# Supplemental_Power_Switch_System.net
KiCad netlist of a schematic drawn in EAGLE
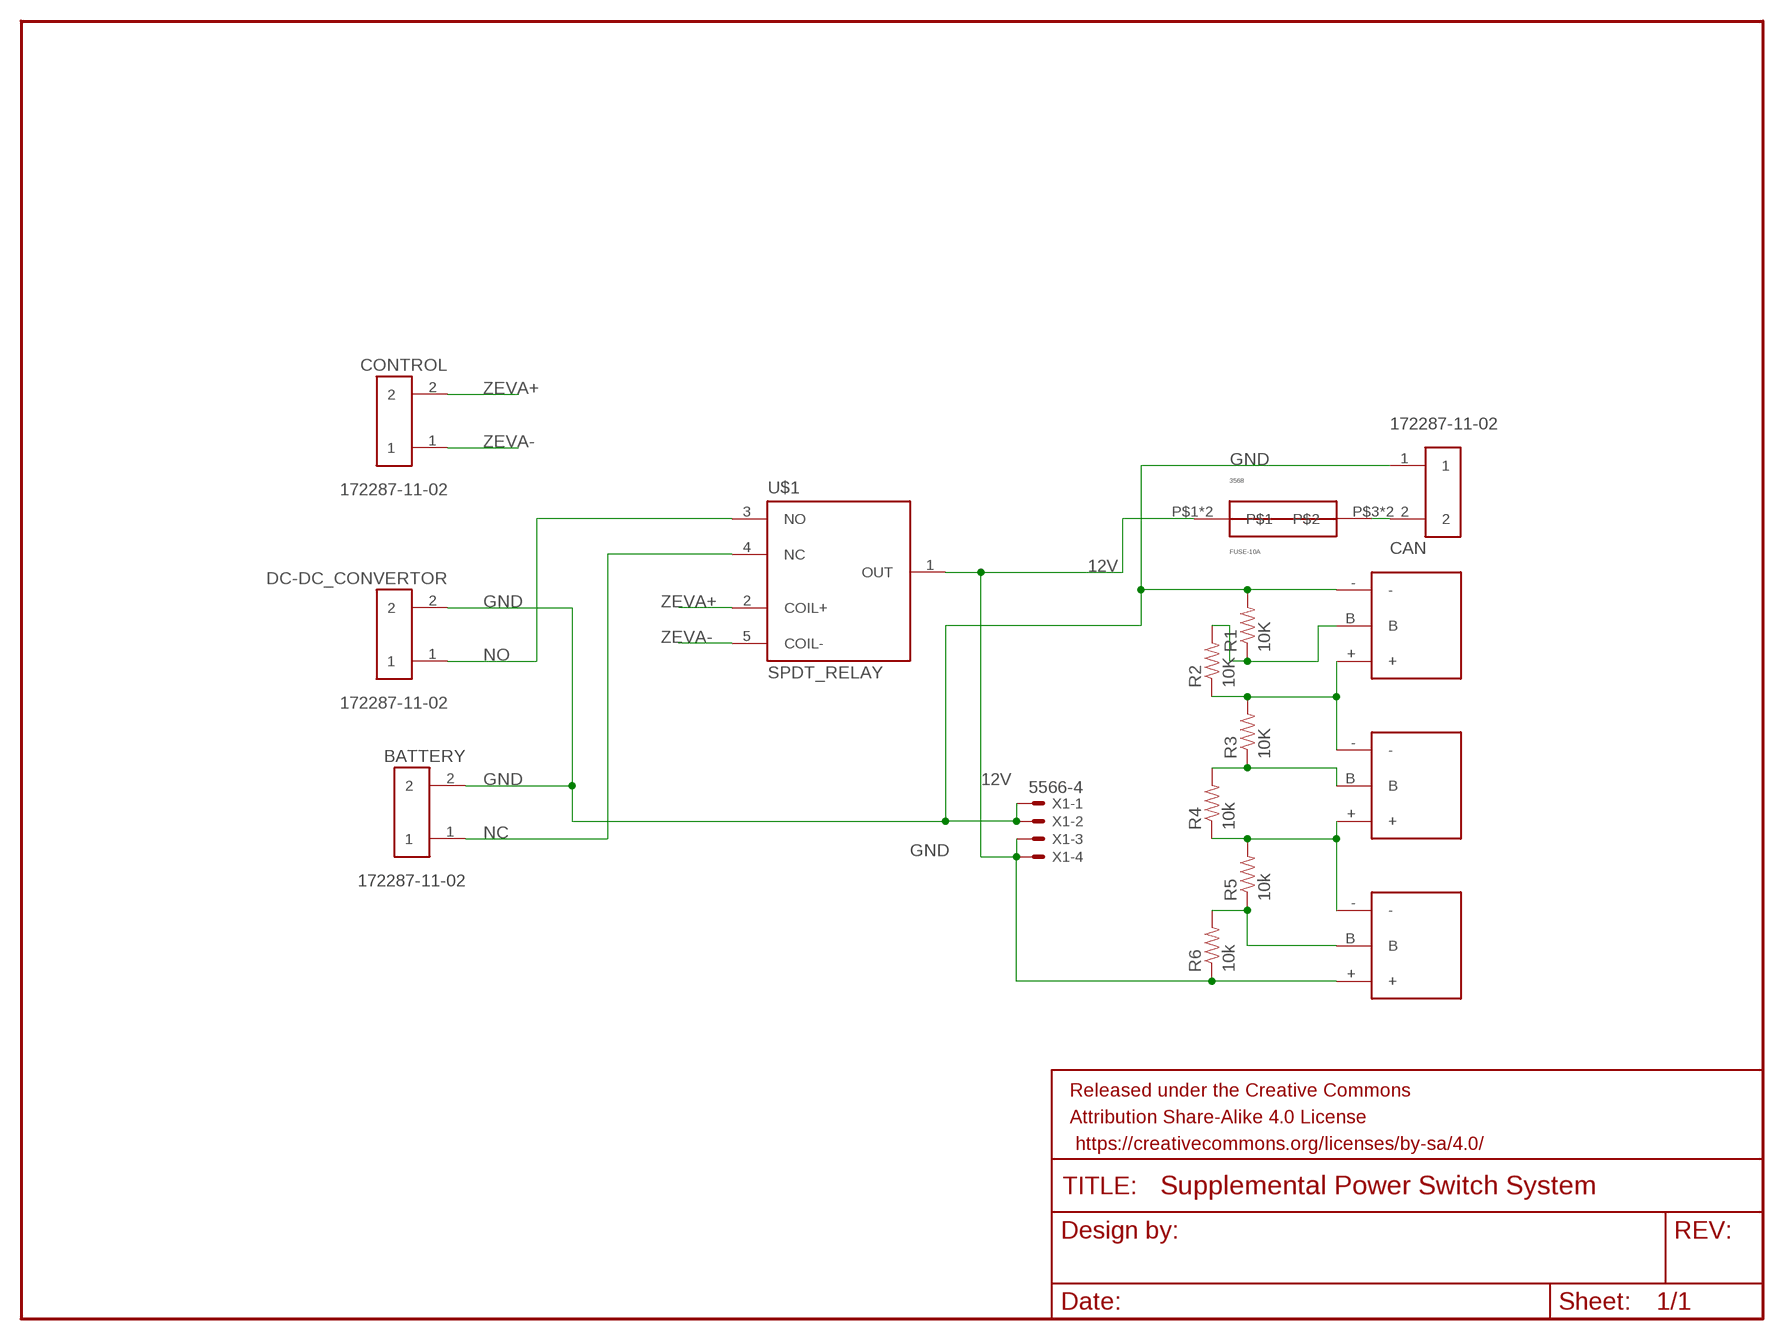
[diagram p0: schematic, sheet 1]

(export (version "E")
  (design (tool "Eeschema 10.0.6"))
  (components
    (comp (ref "BATTERY")
      (value "172287-11-02")
      (footprint "eagle-import:172287-ULTRA-FIT")
      (libsource (lib "eagle-import") (part "172287-11-02"))
    )
    (comp (ref "C1")
      (value "SUPER-CAPACITOR")
      (footprint "eagle-import:DMF")
      (libsource (lib "eagle-import") (part "SUPER-CAPACITOR"))
    )
    (comp (ref "C2")
      (value "SUPER-CAPACITOR")
      (footprint "eagle-import:DMF")
      (libsource (lib "eagle-import") (part "SUPER-CAPACITOR"))
    )
    (comp (ref "C3")
      (value "SUPER-CAPACITOR")
      (footprint "eagle-import:DMF")
      (libsource (lib "eagle-import") (part "SUPER-CAPACITOR"))
    )
    (comp (ref "CAN")
      (value "172287-11-02")
      (footprint "eagle-import:172287-ULTRA-FIT")
      (libsource (lib "eagle-import") (part "172287-11-02"))
    )
    (comp (ref "CONTROL")
      (value "172287-11-02")
      (footprint "eagle-import:172287-ULTRA-FIT")
      (libsource (lib "eagle-import") (part "172287-11-02"))
    )
    (comp (ref "DC-DC_CONVERTOR")
      (value "172287-11-02")
      (footprint "eagle-import:172287-ULTRA-FIT")
      (libsource (lib "eagle-import") (part "172287-11-02"))
    )
    (comp (ref "FRAME1")
      (value "FRAME-LETTERNO_PACKAGE")
      (footprint "eagle-import:DUMMY")
      (fields (field (name "DESIGNER") "Nobody"))
      (libsource (lib "eagle-import") (part "FRAME-LETTERNO_PACKAGE"))
    )
    (comp (ref "FUSE-10A")
      (value "3568")
      (footprint "eagle-import:3568-MINI-297")
      (libsource (lib "eagle-import") (part "3568"))
    )
    (comp (ref "R1")
      (value "10K")
      (footprint "eagle-import:1206")
      (libsource (lib "eagle-import") (part "RESISTOR1206"))
    )
    (comp (ref "R2")
      (value "10K")
      (footprint "eagle-import:1206")
      (libsource (lib "eagle-import") (part "RESISTOR1206"))
    )
    (comp (ref "R3")
      (value "10K")
      (footprint "eagle-import:1206")
      (libsource (lib "eagle-import") (part "RESISTOR1206"))
    )
    (comp (ref "R4")
      (value "10k")
      (footprint "eagle-import:1206")
      (libsource (lib "eagle-import") (part "RESISTOR1206"))
    )
    (comp (ref "R5")
      (value "10k")
      (footprint "eagle-import:1206")
      (libsource (lib "eagle-import") (part "RESISTOR1206"))
    )
    (comp (ref "R6")
      (value "10k")
      (footprint "eagle-import:1206")
      (libsource (lib "eagle-import") (part "RESISTOR1206"))
    )
    (comp (ref "U$1")
      (value "SPDT_RELAY")
      (footprint "eagle-import:G8QN-1C4")
      (libsource (lib "eagle-import") (part "SPDT_RELAY"))
    )
    (comp (ref "X1")
      (value "5566-4")
      (footprint "eagle-import:5566-4")
      (libsource (lib "eagle-import") (part "5566-4"))
    )
  )
  (nets
    (net (code "1") (name "/12V") (class "Default")
      (node (ref "C3") (pin "+") (pinfunction "+_+") (pintype "bidirectional"))
      (node (ref "FUSE-10A") (pin "P$1") (pinfunction "P$1_P$1") (pintype "bidirectional"))
      (node (ref "FUSE-10A") (pin "P$2") (pinfunction "P$1_P$2") (pintype "bidirectional"))
      (node (ref "R6") (pin "1") (pinfunction "1_1") (pintype "passive"))
      (node (ref "U$1") (pin "1") (pinfunction "OUT_1") (pintype "output"))
      (node (ref "X1") (pin "3") (pinfunction "S_3") (pintype "passive"))
      (node (ref "X1") (pin "4") (pinfunction "S_4") (pintype "passive"))
    )
    (net (code "2") (name "/GND") (class "Default")
      (node (ref "BATTERY") (pin "2") (pinfunction "2_2") (pintype "bidirectional"))
      (node (ref "C1") (pin "-") (pinfunction "-_-") (pintype "bidirectional"))
      (node (ref "CAN") (pin "1") (pinfunction "1_1") (pintype "bidirectional"))
      (node (ref "DC-DC_CONVERTOR") (pin "2") (pinfunction "2_2") (pintype "bidirectional"))
      (node (ref "R1") (pin "2") (pinfunction "2_2") (pintype "passive"))
      (node (ref "X1") (pin "1") (pinfunction "S_1") (pintype "passive"))
      (node (ref "X1") (pin "2") (pinfunction "S_2") (pintype "passive"))
    )
    (net (code "3") (name "/NC") (class "Default")
      (node (ref "BATTERY") (pin "1") (pinfunction "1_1") (pintype "bidirectional"))
      (node (ref "U$1") (pin "4") (pinfunction "NC_4") (pintype "input"))
    )
    (net (code "4") (name "/NO") (class "Default")
      (node (ref "DC-DC_CONVERTOR") (pin "1") (pinfunction "1_1") (pintype "bidirectional"))
      (node (ref "U$1") (pin "3") (pinfunction "NO_3") (pintype "input"))
    )
    (net (code "5") (name "/ZEVA+") (class "Default")
      (node (ref "CONTROL") (pin "2") (pinfunction "2_2") (pintype "bidirectional"))
      (node (ref "U$1") (pin "2") (pinfunction "COIL+_2") (pintype "input"))
    )
    (net (code "6") (name "/ZEVA-") (class "Default")
      (node (ref "CONTROL") (pin "1") (pinfunction "1_1") (pintype "bidirectional"))
      (node (ref "U$1") (pin "5") (pinfunction "COIL-_5") (pintype "input"))
    )
    (net (code "7") (name "Net-(C1-Pad+)") (class "Default")
      (node (ref "C1") (pin "+") (pinfunction "+_+") (pintype "bidirectional"))
      (node (ref "C2") (pin "-") (pinfunction "-_-") (pintype "bidirectional"))
      (node (ref "R2") (pin "1") (pinfunction "1_1") (pintype "passive"))
      (node (ref "R3") (pin "2") (pinfunction "2_2") (pintype "passive"))
    )
    (net (code "8") (name "Net-(C1-PadB)") (class "Default")
      (node (ref "C1") (pin "B") (pinfunction "B_B") (pintype "bidirectional"))
      (node (ref "R1") (pin "1") (pinfunction "1_1") (pintype "passive"))
      (node (ref "R2") (pin "2") (pinfunction "2_2") (pintype "passive"))
    )
    (net (code "9") (name "Net-(C2-Pad+)") (class "Default")
      (node (ref "C2") (pin "+") (pinfunction "+_+") (pintype "bidirectional"))
      (node (ref "C3") (pin "-") (pinfunction "-_-") (pintype "bidirectional"))
      (node (ref "R4") (pin "1") (pinfunction "1_1") (pintype "passive"))
      (node (ref "R5") (pin "2") (pinfunction "2_2") (pintype "passive"))
    )
    (net (code "10") (name "Net-(C2-PadB)") (class "Default")
      (node (ref "C2") (pin "B") (pinfunction "B_B") (pintype "bidirectional"))
      (node (ref "R3") (pin "1") (pinfunction "1_1") (pintype "passive"))
      (node (ref "R4") (pin "2") (pinfunction "2_2") (pintype "passive"))
    )
    (net (code "11") (name "Net-(C3-PadB)") (class "Default")
      (node (ref "C3") (pin "B") (pinfunction "B_B") (pintype "bidirectional"))
      (node (ref "R5") (pin "1") (pinfunction "1_1") (pintype "passive"))
      (node (ref "R6") (pin "2") (pinfunction "2_2") (pintype "passive"))
    )
    (net (code "12") (name "Net-(CAN-Pad2)") (class "Default")
      (node (ref "CAN") (pin "2") (pinfunction "2_2") (pintype "bidirectional"))
      (node (ref "FUSE-10A") (pin "P$3") (pinfunction "P$2_P$3") (pintype "bidirectional"))
      (node (ref "FUSE-10A") (pin "P$4") (pinfunction "P$2_P$4") (pintype "bidirectional"))
    )
  )
)
